# TapOnEr_Fules_Erz.net
KiCad netlist of a schematic drawn in EAGLE
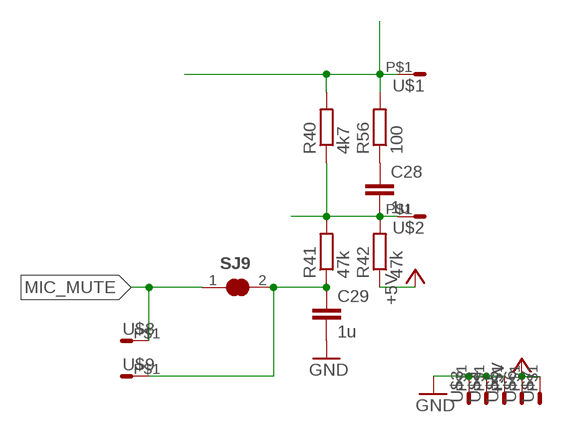
[diagram p0: schematic, sheet 1]

(export (version "E")
  (design (tool "Eeschema 10.0.6"))
  (components
    (comp (ref "C28")
      (value "1u")
      (footprint "eagle-import:C0805")
      (libsource (lib "eagle-import") (part "C-EUC0805"))
    )
    (comp (ref "C29")
      (value "1u")
      (footprint "eagle-import:C0805")
      (libsource (lib "eagle-import") (part "C-EUC0805"))
    )
    (comp (ref "R40")
      (value "4k7")
      (footprint "eagle-import:R0805")
      (libsource (lib "eagle-import") (part "R-EU_R0805"))
    )
    (comp (ref "R41")
      (value "47k")
      (footprint "eagle-import:R0805")
      (libsource (lib "eagle-import") (part "R-EU_R0805"))
    )
    (comp (ref "R42")
      (value "47k")
      (footprint "eagle-import:R0805")
      (libsource (lib "eagle-import") (part "R-EU_R0805"))
    )
    (comp (ref "R56")
      (value "100")
      (footprint "eagle-import:R0805")
      (libsource (lib "eagle-import") (part "R-EU_R0805"))
    )
    (comp (ref "SJ9")
      (value "SJC")
      (footprint "eagle-import:SJC")
      (libsource (lib "eagle-import") (part "SJC"))
    )
    (comp (ref "U$1")
      (value "PADSMD")
      (footprint "eagle-import:PAD_SMD")
      (libsource (lib "eagle-import") (part "PADSMD"))
    )
    (comp (ref "U$2")
      (value "PADSMD")
      (footprint "eagle-import:PAD_SMD")
      (libsource (lib "eagle-import") (part "PADSMD"))
    )
    (comp (ref "U$3")
      (value "PADSMD")
      (footprint "eagle-import:PAD_SMD")
      (libsource (lib "eagle-import") (part "PADSMD"))
    )
    (comp (ref "U$4")
      (value "PADSMD")
      (footprint "eagle-import:PAD_SMD")
      (libsource (lib "eagle-import") (part "PADSMD"))
    )
    (comp (ref "U$5")
      (value "PADSMD")
      (footprint "eagle-import:PAD_SMD")
      (libsource (lib "eagle-import") (part "PADSMD"))
    )
    (comp (ref "U$6")
      (value "PADSMD")
      (footprint "eagle-import:PAD_SMD")
      (libsource (lib "eagle-import") (part "PADSMD"))
    )
    (comp (ref "U$7")
      (value "PADSMD")
      (footprint "eagle-import:PAD_SMD")
      (libsource (lib "eagle-import") (part "PADSMD"))
    )
    (comp (ref "U$8")
      (value "PADSMD")
      (footprint "eagle-import:PAD_SMD")
      (libsource (lib "eagle-import") (part "PADSMD"))
    )
    (comp (ref "U$9")
      (value "PADSMD")
      (footprint "eagle-import:PAD_SMD")
      (libsource (lib "eagle-import") (part "PADSMD"))
    )
  )
  (nets
    (net (code "1") (name "+5V") (class "Default")
      (node (ref "R42") (pin "1") (pinfunction "1_1") (pintype "passive"))
      (node (ref "U$6") (pin "P$1") (pinfunction "2_P$1") (pintype "passive"))
      (node (ref "U$7") (pin "P$1") (pinfunction "2_P$1") (pintype "passive"))
    )
    (net (code "2") (name "GND") (class "Default")
      (node (ref "C29") (pin "2") (pinfunction "2_2") (pintype "passive"))
      (node (ref "U$3") (pin "P$1") (pinfunction "2_P$1") (pintype "passive"))
      (node (ref "U$4") (pin "P$1") (pinfunction "2_P$1") (pintype "passive"))
      (node (ref "U$5") (pin "P$1") (pinfunction "2_P$1") (pintype "passive"))
    )
    (net (code "3") (name "MIC_MUTE") (class "Default")
      (node (ref "SJ9") (pin "1") (pinfunction "1_1") (pintype "passive"))
      (node (ref "U$8") (pin "P$1") (pinfunction "2_P$1") (pintype "passive"))
    )
    (net (code "4") (name "Net-(C28-Pad1)") (class "Default")
      (node (ref "C28") (pin "1") (pinfunction "1_1") (pintype "passive"))
      (node (ref "R56") (pin "1") (pinfunction "1_1") (pintype "passive"))
    )
    (net (code "5") (name "Net-(U$1-2)") (class "Default")
      (node (ref "R40") (pin "2") (pinfunction "2_2") (pintype "passive"))
      (node (ref "R56") (pin "2") (pinfunction "2_2") (pintype "passive"))
      (node (ref "U$1") (pin "P$1") (pinfunction "2_P$1") (pintype "passive"))
    )
    (net (code "6") (name "Net-(U$2-2)") (class "Default")
      (node (ref "C28") (pin "2") (pinfunction "2_2") (pintype "passive"))
      (node (ref "R40") (pin "1") (pinfunction "1_1") (pintype "passive"))
      (node (ref "R41") (pin "2") (pinfunction "2_2") (pintype "passive"))
      (node (ref "R42") (pin "2") (pinfunction "2_2") (pintype "passive"))
      (node (ref "U$2") (pin "P$1") (pinfunction "2_P$1") (pintype "passive"))
    )
    (net (code "7") (name "Net-(U$9-2)") (class "Default")
      (node (ref "C29") (pin "1") (pinfunction "1_1") (pintype "passive"))
      (node (ref "R41") (pin "1") (pinfunction "1_1") (pintype "passive"))
      (node (ref "SJ9") (pin "2") (pinfunction "2_2") (pintype "passive"))
      (node (ref "U$9") (pin "P$1") (pinfunction "2_P$1") (pintype "passive"))
    )
  )
)
